# AVS.net
KiCad netlist of a schematic drawn in EasyEDA
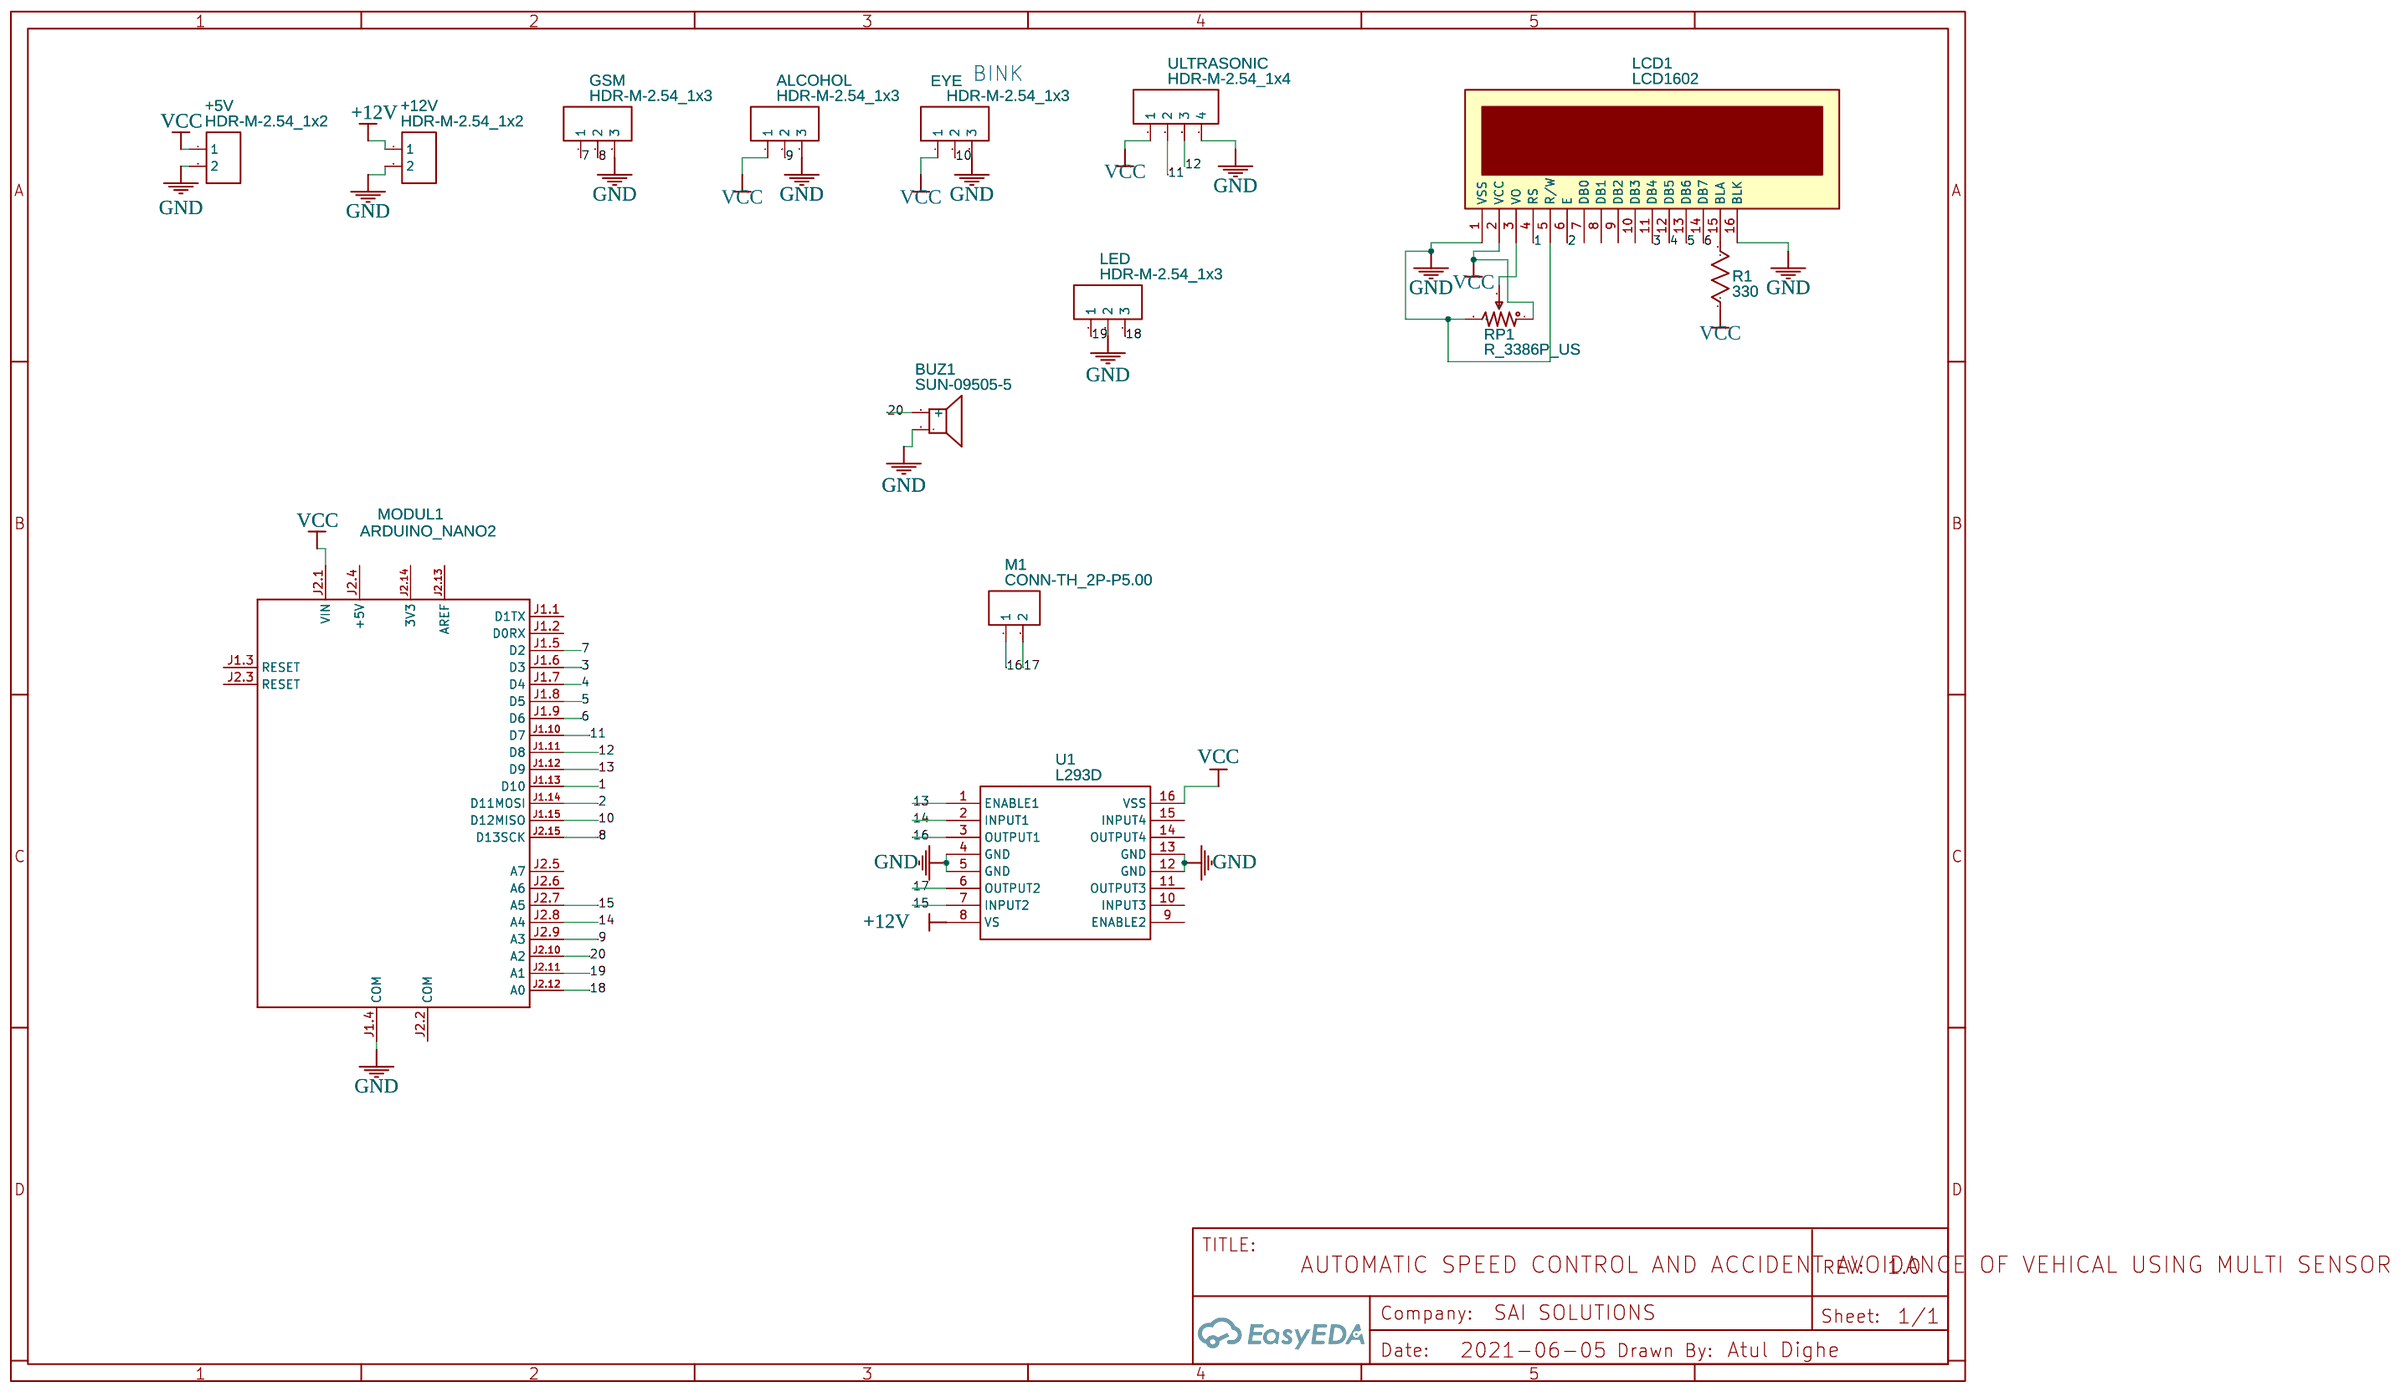
[diagram p0: CONTROLLER BOARD]
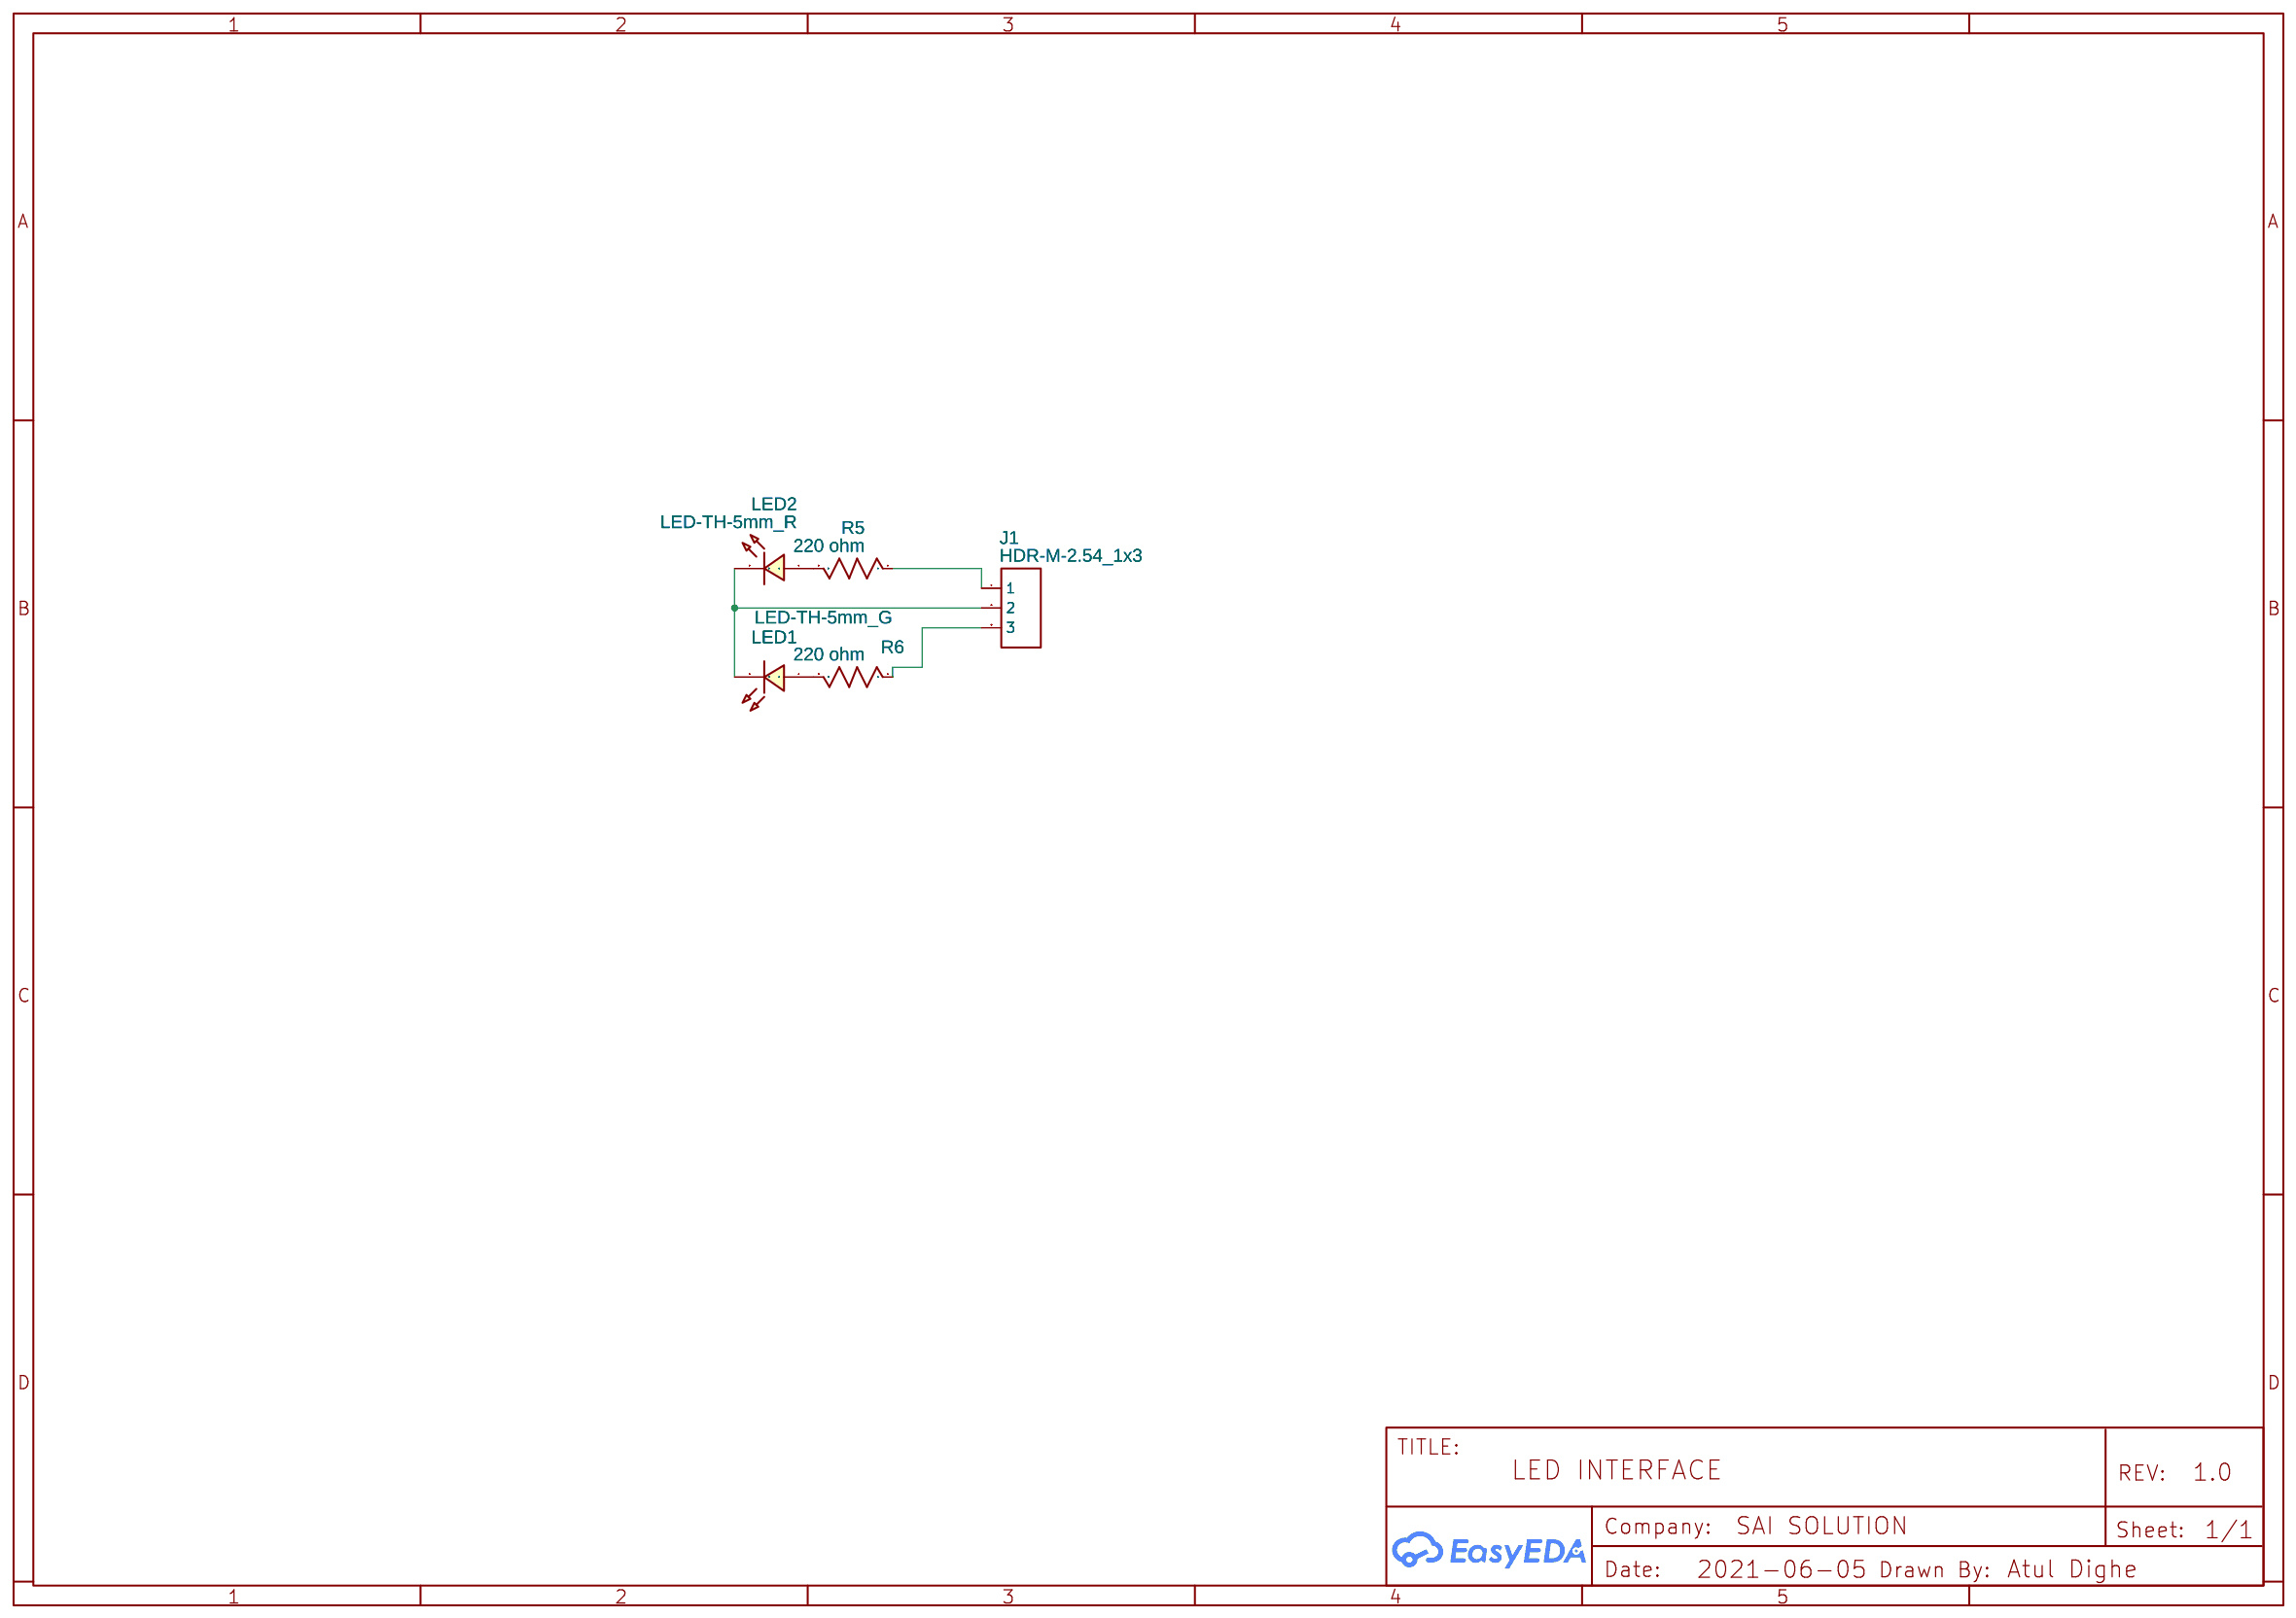
[diagram p1: LED INTERFACE]

(export (version "E")
  (design (tool "Eeschema 10.0.6"))
  (components
    (comp (ref "+5V")
      (value "HDR-M-2.54_1x2")
      (fields (field (name "BOM_Supplier Part") "C124375"))
      (libsource (lib "") (part "HDR-M-2.54_1x2_1"))
    )
    (comp (ref "+12V")
      (value "HDR-M-2.54_1x2")
      (fields (field (name "BOM_Supplier Part") "C124375"))
      (libsource (lib "") (part "HDR-M-2.54_1x2"))
    )
    (comp (ref "ALCOHOL")
      (value "HDR-M-2.54_1x3")
      (fields (field (name "BOM_Supplier Part") "C180248"))
      (libsource (lib "") (part "HDR-M-2.54_1x3_1"))
    )
    (comp (ref "BUZ1")
      (value "SUN-09505-5")
      (fields (field (name "BOM_Supplier Part") "C2862"))
      (libsource (lib "") (part "SUN-09505-5"))
    )
    (comp (ref "EYE")
      (value "HDR-M-2.54_1x3")
      (fields (field (name "BOM_Supplier Part") "C180248"))
      (libsource (lib "") (part "HDR-M-2.54_1x3_3"))
    )
    (comp (ref "GSM")
      (value "HDR-M-2.54_1x3")
      (fields (field (name "BOM_Supplier Part") "C180248"))
      (libsource (lib "") (part "HDR-M-2.54_1x3_2"))
    )
    (comp (ref "LCD1")
      (value "LCD1602")
      (fields
        (field (name "BOM_Manufacturer Part") "LCM1602K-NSW-BBW")
        (field (name "BOM_Supplier Part") "C83275")
      )
      (libsource (lib "") (part "LCD1602"))
    )
    (comp (ref "LED")
      (value "HDR-M-2.54_1x3")
      (fields (field (name "BOM_Supplier Part") "C180248"))
      (libsource (lib "") (part "HDR-M-2.54_1x3"))
    )
    (comp (ref "M1") (value "CONN-TH_2P-P5.00") (libsource (lib "") (part "CONN-TH_2P-P5.00")))
    (comp (ref "MODUL1") (value "ARDUINO_NANO2") (libsource (lib "") (part "ARDUINO_NANO2")))
    (comp (ref "R1") (value "330") (libsource (lib "") (part "R_AXIAL-0.4_US")))
    (comp (ref "RP1") (value "R_3386P_US") (libsource (lib "") (part "R_3386P_US")))
    (comp (ref "U1")
      (value "L293D")
      (fields (field (name "BOM_Supplier Part") "C12340"))
      (libsource (lib "") (part "L293D"))
    )
    (comp (ref "ULTRASONIC")
      (value "HDR-M-2.54_1x4")
      (fields (field (name "BOM_Supplier Part") "C124378"))
      (libsource (lib "") (part "HDR-M-2.54_1x4"))
    )
    (comp (ref "J1")
      (value "HDR-M-2.54_1x3")
      (fields (field (name "BOM_Supplier Part") "C180248"))
      (libsource (lib "") (part "HDR-M-2.54_1x3"))
    )
    (comp (ref "LED1")
      (value "LED-TH-5mm_G")
      (fields
        (field (name "BOM_Manufacturer Part") "333-2SYGD/S530-E2")
        (field (name "BOM_Supplier Part") "C88163")
      )
      (libsource (lib "") (part "LED-TH-5mm_G"))
    )
    (comp (ref "LED2")
      (value "LED-TH-5mm_R")
      (fields
        (field (name "BOM_Manufacturer Part") "333-2SURD/S530-A3")
        (field (name "BOM_Supplier Part") "C87271")
      )
      (libsource (lib "") (part "LED-TH-5mm_R"))
    )
    (comp (ref "R5") (value "220 ohm") (libsource (lib "") (part "R_AXIAL-0.4_US")))
    (comp (ref "R6") (value "220 ohm") (libsource (lib "") (part "R_AXIAL-0.4_US")))
  )
  (nets
    (net (code "1") (name "+12V") (class "Default")
      (node (ref "+12V") (pin "1") (pinfunction "1_1") (pintype "unspecified"))
      (node (ref "U1") (pin "8") (pinfunction "VS_8") (pintype "unspecified"))
    )
    (net (code "2") (name "1") (class "Default")
      (node (ref "LCD1") (pin "4") (pinfunction "RS_4") (pintype "unspecified"))
      (node (ref "MODUL1") (pin "J1.13") (pinfunction "D10_J1.13") (pintype "unspecified"))
    )
    (net (code "3") (name "2") (class "Default")
      (node (ref "LCD1") (pin "6") (pinfunction "E_6") (pintype "unspecified"))
      (node (ref "MODUL1") (pin "J1.14") (pinfunction "D11MOSI_J1.14") (pintype "unspecified"))
    )
    (net (code "4") (name "3") (class "Default")
      (node (ref "LCD1") (pin "11") (pinfunction "DB4_11") (pintype "unspecified"))
      (node (ref "MODUL1") (pin "J1.6") (pinfunction "D3_J1.6") (pintype "unspecified"))
    )
    (net (code "5") (name "4") (class "Default")
      (node (ref "LCD1") (pin "12") (pinfunction "DB5_12") (pintype "unspecified"))
      (node (ref "MODUL1") (pin "J1.7") (pinfunction "D4_J1.7") (pintype "unspecified"))
    )
    (net (code "6") (name "5") (class "Default")
      (node (ref "LCD1") (pin "13") (pinfunction "DB6_13") (pintype "unspecified"))
      (node (ref "MODUL1") (pin "J1.8") (pinfunction "D5_J1.8") (pintype "unspecified"))
    )
    (net (code "7") (name "6") (class "Default")
      (node (ref "LCD1") (pin "14") (pinfunction "DB7_14") (pintype "unspecified"))
      (node (ref "MODUL1") (pin "J1.9") (pinfunction "D6_J1.9") (pintype "unspecified"))
    )
    (net (code "8") (name "7") (class "Default")
      (node (ref "GSM") (pin "1") (pinfunction "1_1") (pintype "input"))
      (node (ref "MODUL1") (pin "J1.5") (pinfunction "D2_J1.5") (pintype "unspecified"))
    )
    (net (code "9") (name "8") (class "Default")
      (node (ref "GSM") (pin "2") (pinfunction "2_2") (pintype "input"))
      (node (ref "MODUL1") (pin "J2.15") (pinfunction "D13SCK_J2.15") (pintype "unspecified"))
    )
    (net (code "10") (name "9") (class "Default")
      (node (ref "ALCOHOL") (pin "2") (pinfunction "2_2") (pintype "input"))
      (node (ref "MODUL1") (pin "J2.9") (pinfunction "A3_J2.9") (pintype "unspecified"))
    )
    (net (code "11") (name "10") (class "Default")
      (node (ref "EYE") (pin "2") (pinfunction "2_2") (pintype "input"))
      (node (ref "MODUL1") (pin "J1.15") (pinfunction "D12MISO_J1.15") (pintype "unspecified"))
    )
    (net (code "12") (name "11") (class "Default")
      (node (ref "MODUL1") (pin "J1.10") (pinfunction "D7_J1.10") (pintype "unspecified"))
      (node (ref "ULTRASONIC") (pin "2") (pinfunction "2_2") (pintype "unspecified"))
    )
    (net (code "13") (name "12") (class "Default")
      (node (ref "MODUL1") (pin "J1.11") (pinfunction "D8_J1.11") (pintype "unspecified"))
      (node (ref "ULTRASONIC") (pin "3") (pinfunction "3_3") (pintype "unspecified"))
    )
    (net (code "14") (name "13") (class "Default")
      (node (ref "MODUL1") (pin "J1.12") (pinfunction "D9_J1.12") (pintype "unspecified"))
      (node (ref "U1") (pin "1") (pinfunction "ENABLE1_1") (pintype "unspecified"))
    )
    (net (code "15") (name "14") (class "Default")
      (node (ref "MODUL1") (pin "J2.8") (pinfunction "A4_J2.8") (pintype "unspecified"))
      (node (ref "U1") (pin "2") (pinfunction "INPUT1_2") (pintype "unspecified"))
    )
    (net (code "16") (name "15") (class "Default")
      (node (ref "MODUL1") (pin "J2.7") (pinfunction "A5_J2.7") (pintype "unspecified"))
      (node (ref "U1") (pin "7") (pinfunction "INPUT2_7") (pintype "unspecified"))
    )
    (net (code "17") (name "16") (class "Default")
      (node (ref "M1") (pin "1") (pinfunction "1_1") (pintype "unspecified"))
      (node (ref "U1") (pin "3") (pinfunction "OUTPUT1_3") (pintype "unspecified"))
    )
    (net (code "18") (name "17") (class "Default")
      (node (ref "M1") (pin "2") (pinfunction "2_2") (pintype "unspecified"))
      (node (ref "U1") (pin "6") (pinfunction "OUTPUT2_6") (pintype "unspecified"))
    )
    (net (code "19") (name "18") (class "Default")
      (node (ref "LED") (pin "3") (pinfunction "3_3") (pintype "input"))
      (node (ref "MODUL1") (pin "J2.12") (pinfunction "A0_J2.12") (pintype "unspecified"))
    )
    (net (code "20") (name "19") (class "Default")
      (node (ref "LED") (pin "1") (pinfunction "1_1") (pintype "input"))
      (node (ref "MODUL1") (pin "J2.11") (pinfunction "A1_J2.11") (pintype "unspecified"))
    )
    (net (code "21") (name "20") (class "Default")
      (node (ref "BUZ1") (pin "1") (pinfunction "+_1") (pintype "unspecified"))
      (node (ref "MODUL1") (pin "J2.10") (pinfunction "A2_J2.10") (pintype "unspecified"))
    )
    (net (code "22") (name "GND") (class "Default")
      (node (ref "+12V") (pin "2") (pinfunction "2_2") (pintype "unspecified"))
      (node (ref "+5V") (pin "2") (pinfunction "2_2") (pintype "unspecified"))
      (node (ref "ALCOHOL") (pin "3") (pinfunction "3_3") (pintype "input"))
      (node (ref "BUZ1") (pin "2") (pinfunction "2_2") (pintype "unspecified"))
      (node (ref "EYE") (pin "3") (pinfunction "3_3") (pintype "input"))
      (node (ref "GSM") (pin "3") (pinfunction "3_3") (pintype "input"))
      (node (ref "LCD1") (pin "1") (pinfunction "VSS_1") (pintype "unspecified"))
      (node (ref "LCD1") (pin "16") (pinfunction "BLK_16") (pintype "unspecified"))
      (node (ref "LCD1") (pin "5") (pinfunction "R/W_5") (pintype "unspecified"))
      (node (ref "LED") (pin "2") (pinfunction "2_2") (pintype "input"))
      (node (ref "MODUL1") (pin "J1.4") (pinfunction "COM_J1.4") (pintype "passive"))
      (node (ref "RP1") (pin "3") (pinfunction "3_3") (pintype "unspecified"))
      (node (ref "U1") (pin "12") (pinfunction "GND_12") (pintype "unspecified"))
      (node (ref "U1") (pin "13") (pinfunction "GND_13") (pintype "unspecified"))
      (node (ref "U1") (pin "4") (pinfunction "GND_4") (pintype "unspecified"))
      (node (ref "U1") (pin "5") (pinfunction "GND_5") (pintype "unspecified"))
      (node (ref "ULTRASONIC") (pin "4") (pinfunction "4_4") (pintype "unspecified"))
    )
    (net (code "23") (name "Net-(J1-Pad1)") (class "Default")
      (node (ref "J1") (pin "1") (pinfunction "1_1") (pintype "input"))
      (node (ref "R5") (pin "1") (pinfunction "1_1") (pintype "unspecified"))
    )
    (net (code "24") (name "Net-(J1-Pad2)") (class "Default")
      (node (ref "J1") (pin "2") (pinfunction "2_2") (pintype "input"))
      (node (ref "LED1") (pin "2") (pinfunction "2_2") (pintype "unspecified"))
      (node (ref "LED2") (pin "2") (pinfunction "2_2") (pintype "unspecified"))
    )
    (net (code "25") (name "Net-(J1-Pad3)") (class "Default")
      (node (ref "J1") (pin "3") (pinfunction "3_3") (pintype "input"))
      (node (ref "R6") (pin "1") (pinfunction "1_1") (pintype "unspecified"))
    )
    (net (code "26") (name "Net-(LCD1-BLA)") (class "Default")
      (node (ref "LCD1") (pin "15") (pinfunction "BLA_15") (pintype "unspecified"))
      (node (ref "R1") (pin "2") (pinfunction "2_2") (pintype "unspecified"))
    )
    (net (code "27") (name "Net-(LCD1-VO)") (class "Default")
      (node (ref "LCD1") (pin "3") (pinfunction "VO_3") (pintype "unspecified"))
      (node (ref "RP1") (pin "2") (pinfunction "2_2") (pintype "unspecified"))
    )
    (net (code "28") (name "Net-(LED1-Pad1)") (class "Default")
      (node (ref "LED1") (pin "1") (pinfunction "1_1") (pintype "unspecified"))
      (node (ref "R6") (pin "2") (pinfunction "2_2") (pintype "unspecified"))
    )
    (net (code "29") (name "Net-(LED2-Pad1)") (class "Default")
      (node (ref "LED2") (pin "1") (pinfunction "1_1") (pintype "unspecified"))
      (node (ref "R5") (pin "2") (pinfunction "2_2") (pintype "unspecified"))
    )
    (net (code "30") (name "VCC") (class "Default")
      (node (ref "+5V") (pin "1") (pinfunction "1_1") (pintype "unspecified"))
      (node (ref "ALCOHOL") (pin "1") (pinfunction "1_1") (pintype "input"))
      (node (ref "EYE") (pin "1") (pinfunction "1_1") (pintype "input"))
      (node (ref "LCD1") (pin "2") (pinfunction "VCC_2") (pintype "unspecified"))
      (node (ref "MODUL1") (pin "J2.1") (pinfunction "VIN_J2.1") (pintype "passive"))
      (node (ref "R1") (pin "1") (pinfunction "1_1") (pintype "unspecified"))
      (node (ref "RP1") (pin "1") (pinfunction "1_1") (pintype "unspecified"))
      (node (ref "U1") (pin "16") (pinfunction "VSS_16") (pintype "unspecified"))
      (node (ref "ULTRASONIC") (pin "1") (pinfunction "1_1") (pintype "unspecified"))
    )
    (net (code "31") (name "unconnected-(LCD1-DB0-Pad7)") (class "Default")
      (node (ref "LCD1") (pin "7") (pinfunction "DB0_7") (pintype "unspecified"))
    )
    (net (code "32") (name "unconnected-(LCD1-DB1-Pad8)") (class "Default")
      (node (ref "LCD1") (pin "8") (pinfunction "DB1_8") (pintype "unspecified"))
    )
    (net (code "33") (name "unconnected-(LCD1-DB2-Pad9)") (class "Default")
      (node (ref "LCD1") (pin "9") (pinfunction "DB2_9") (pintype "unspecified"))
    )
    (net (code "34") (name "unconnected-(LCD1-DB3-Pad10)") (class "Default")
      (node (ref "LCD1") (pin "10") (pinfunction "DB3_10") (pintype "unspecified"))
    )
    (net (code "35") (name "unconnected-(MODUL1-+5V-PadJ2.4)") (class "Default")
      (node (ref "MODUL1") (pin "J2.4") (pinfunction "+5V_J2.4") (pintype "passive"))
    )
    (net (code "36") (name "unconnected-(MODUL1-3V3-PadJ2.14)") (class "Default")
      (node (ref "MODUL1") (pin "J2.14") (pinfunction "3V3_J2.14") (pintype "passive"))
    )
    (net (code "37") (name "unconnected-(MODUL1-A6-PadJ2.6)") (class "Default")
      (node (ref "MODUL1") (pin "J2.6") (pinfunction "A6_J2.6") (pintype "unspecified"))
    )
    (net (code "38") (name "unconnected-(MODUL1-A7-PadJ2.5)") (class "Default")
      (node (ref "MODUL1") (pin "J2.5") (pinfunction "A7_J2.5") (pintype "unspecified"))
    )
    (net (code "39") (name "unconnected-(MODUL1-AREF-PadJ2.13)") (class "Default")
      (node (ref "MODUL1") (pin "J2.13") (pinfunction "AREF_J2.13") (pintype "passive"))
    )
    (net (code "40") (name "unconnected-(MODUL1-COM-PadJ2.2)") (class "Default")
      (node (ref "MODUL1") (pin "J2.2") (pinfunction "COM_J2.2") (pintype "passive"))
    )
    (net (code "41") (name "unconnected-(MODUL1-D0RX-PadJ1.2)") (class "Default")
      (node (ref "MODUL1") (pin "J1.2") (pinfunction "D0RX_J1.2") (pintype "unspecified"))
    )
    (net (code "42") (name "unconnected-(MODUL1-D1TX-PadJ1.1)") (class "Default")
      (node (ref "MODUL1") (pin "J1.1") (pinfunction "D1TX_J1.1") (pintype "unspecified"))
    )
    (net (code "43") (name "unconnected-(MODUL1-RESET-PadJ1.3)") (class "Default")
      (node (ref "MODUL1") (pin "J1.3") (pinfunction "RESET_J1.3") (pintype "unspecified"))
    )
    (net (code "44") (name "unconnected-(MODUL1-RESET-PadJ2.3)") (class "Default")
      (node (ref "MODUL1") (pin "J2.3") (pinfunction "RESET_J2.3") (pintype "unspecified"))
    )
    (net (code "45") (name "unconnected-(U1-ENABLE2-Pad9)") (class "Default")
      (node (ref "U1") (pin "9") (pinfunction "ENABLE2_9") (pintype "unspecified"))
    )
    (net (code "46") (name "unconnected-(U1-INPUT3-Pad10)") (class "Default")
      (node (ref "U1") (pin "10") (pinfunction "INPUT3_10") (pintype "unspecified"))
    )
    (net (code "47") (name "unconnected-(U1-INPUT4-Pad15)") (class "Default")
      (node (ref "U1") (pin "15") (pinfunction "INPUT4_15") (pintype "unspecified"))
    )
    (net (code "48") (name "unconnected-(U1-OUTPUT3-Pad11)") (class "Default")
      (node (ref "U1") (pin "11") (pinfunction "OUTPUT3_11") (pintype "unspecified"))
    )
    (net (code "49") (name "unconnected-(U1-OUTPUT4-Pad14)") (class "Default")
      (node (ref "U1") (pin "14") (pinfunction "OUTPUT4_14") (pintype "unspecified"))
    )
  )
)
